# Power_PCB.net
KiCad netlist of a schematic drawn in EAGLE
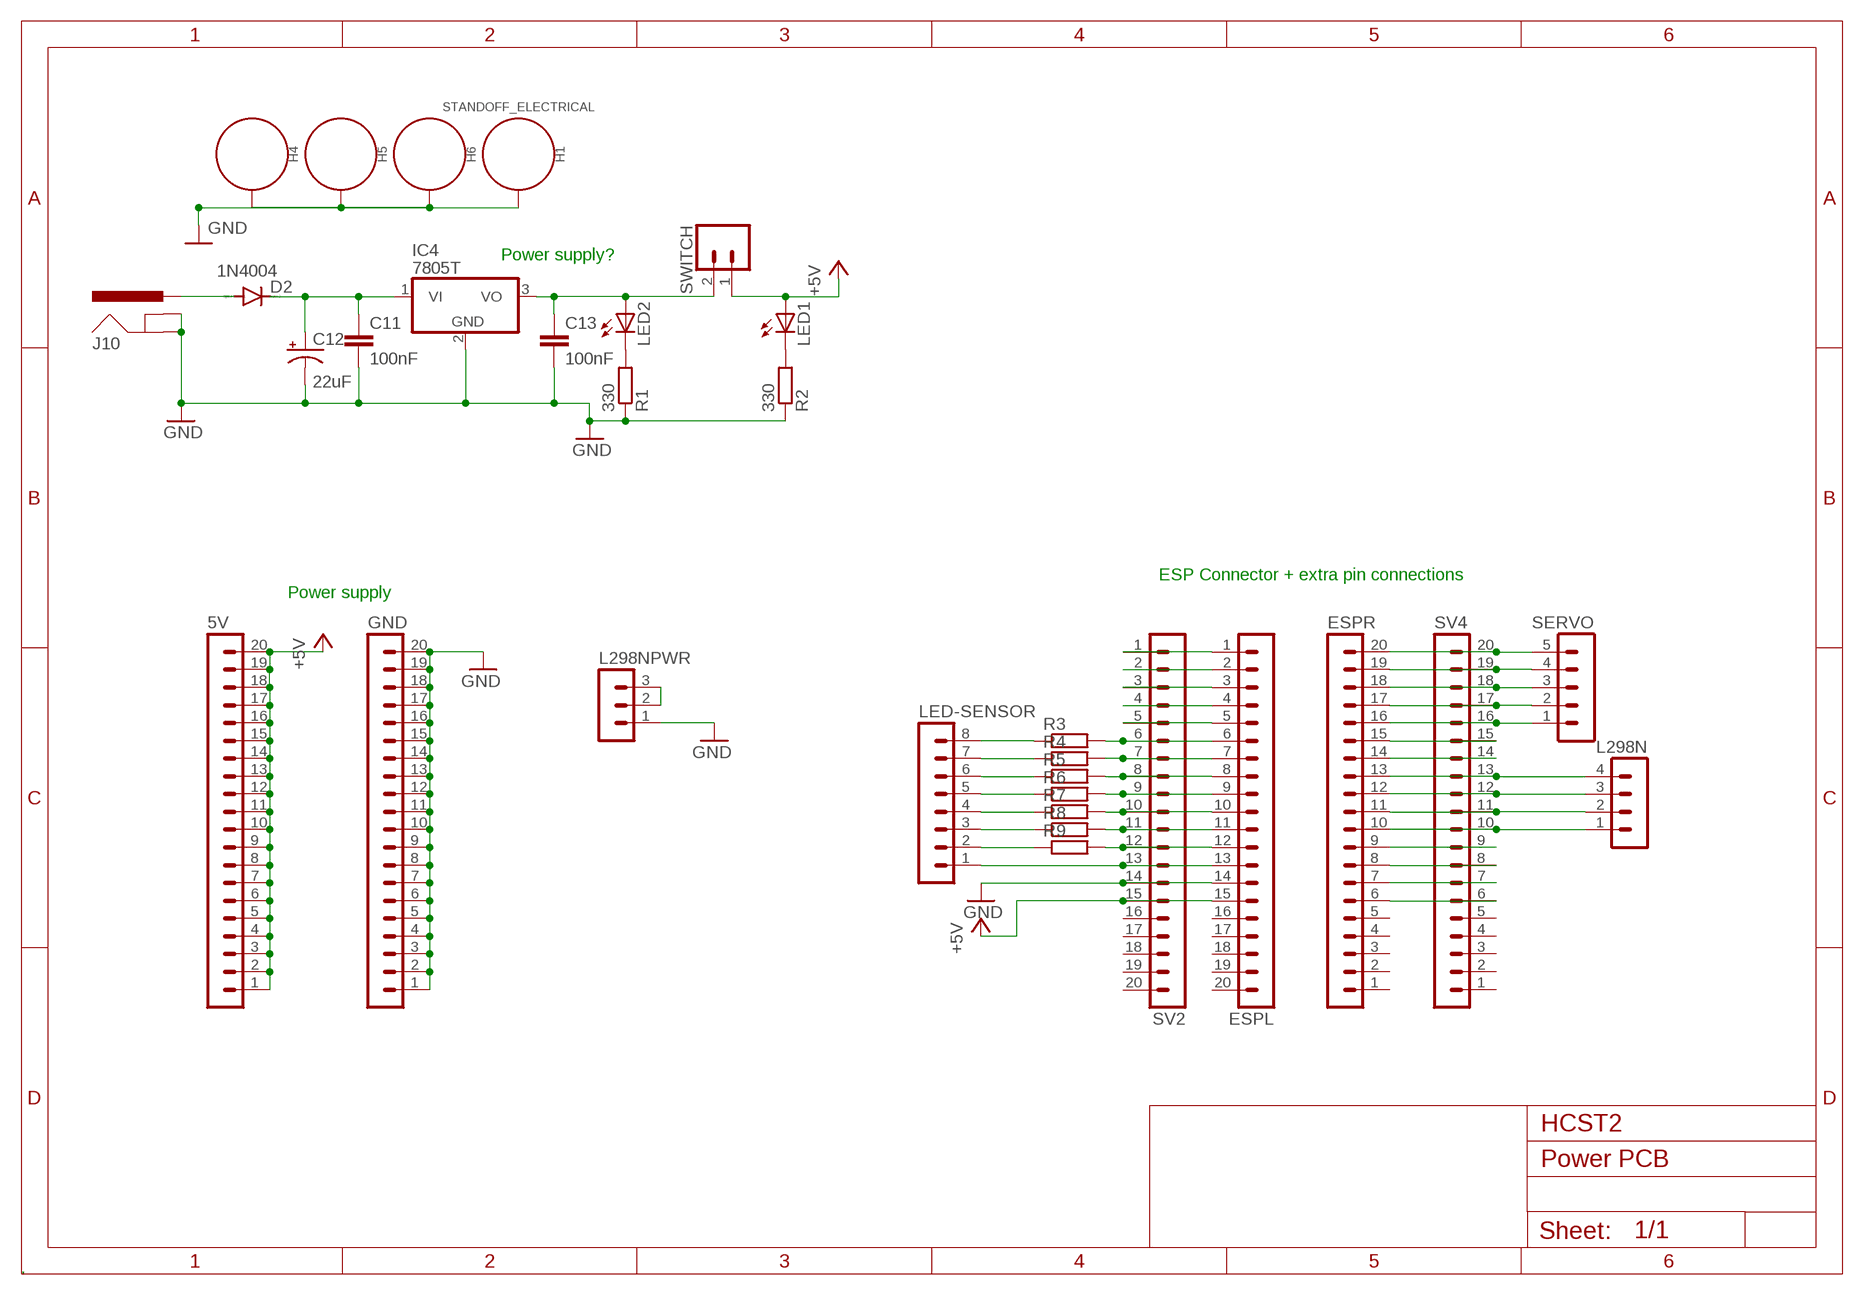
[diagram p0: schematic, sheet 1]

(export (version "E")
  (design (tool "Eeschema 10.0.6"))
  (components
    (comp (ref "5V")
      (value "MA20-1")
      (footprint "eagle-import:MA20-1")
      (libsource (lib "eagle-import") (part "MA20-1"))
    )
    (comp (ref "C11")
      (value "100nF")
      (footprint "eagle-import:C2.5-2")
      (libsource (lib "eagle-import") (part "C2.5/2"))
    )
    (comp (ref "C12")
      (value "22uF")
      (footprint "eagle-import:E2,5-7")
      (libsource (lib "eagle-import") (part "CPOL-USE2.5-7"))
    )
    (comp (ref "C13")
      (value "100nF")
      (footprint "eagle-import:C2.5-2")
      (libsource (lib "eagle-import") (part "C2.5/2"))
    )
    (comp (ref "D2")
      (value "1N4004")
      (footprint "eagle-import:DO41-10")
      (libsource (lib "eagle-import") (part "1N4004"))
    )
    (comp (ref "ESPL")
      (value "MA20-1")
      (footprint "eagle-import:MA20-1")
      (libsource (lib "eagle-import") (part "MA20-1"))
    )
    (comp (ref "ESPR")
      (value "MA20-1")
      (footprint "eagle-import:MA20-1")
      (libsource (lib "eagle-import") (part "MA20-1"))
    )
    (comp (ref "GND")
      (value "MA20-1")
      (footprint "eagle-import:MA20-1")
      (libsource (lib "eagle-import") (part "MA20-1"))
    )
    (comp (ref "H1")
      (value "STANDOFF_ELECTRICAL")
      (footprint "eagle-import:STANDOFF-ELECTRICAL")
      (libsource (lib "eagle-import") (part "STANDOFF_ELECTRICAL"))
    )
    (comp (ref "H4")
      (value "STANDOFF_ELECTRICAL")
      (footprint "eagle-import:STANDOFF-ELECTRICAL")
      (libsource (lib "eagle-import") (part "SparkFun-Hardware_519_STANDOFF_ELECTRICAL"))
    )
    (comp (ref "H5")
      (value "STANDOFF_ELECTRICAL")
      (footprint "eagle-import:STANDOFF-ELECTRICAL")
      (libsource (lib "eagle-import") (part "SparkFun-Hardware_519_STANDOFF_ELECTRICAL"))
    )
    (comp (ref "H6")
      (value "STANDOFF_ELECTRICAL")
      (footprint "eagle-import:STANDOFF-ELECTRICAL")
      (libsource (lib "eagle-import") (part "SparkFun-Hardware_519_STANDOFF_ELECTRICAL"))
    )
    (comp (ref "IC4")
      (value "7805T")
      (footprint "eagle-import:TO220H")
      (libsource (lib "eagle-import") (part "78T05"))
    )
    (comp (ref "J10")
      (value "EL311-ROBOT_SPARKFUN-CONNECTORS_POWER_JACKPTH")
      (footprint "eagle-import:EL311-ROBOT_SPARKFUN-CONNECTORS_POWER_JACK_PTH")
      (libsource (lib "eagle-import") (part "EL311-ROBOT_SPARKFUN-CONNECTORS_POWER_JACKPTH"))
    )
    (comp (ref "L298N")
      (value "MA04-1")
      (footprint "eagle-import:MA04-1")
      (libsource (lib "eagle-import") (part "MA04-1"))
    )
    (comp (ref "L298NPWR")
      (value "MA03-1")
      (footprint "eagle-import:MA03-1")
      (libsource (lib "eagle-import") (part "MA03-1"))
    )
    (comp (ref "LED-SENSOR")
      (value "MA08-1")
      (footprint "eagle-import:MA08-1")
      (libsource (lib "eagle-import") (part "MA08-1"))
    )
    (comp (ref "LED1")
      (value "LED3MM")
      (footprint "eagle-import:LED3MM")
      (libsource (lib "eagle-import") (part "LED3MM"))
    )
    (comp (ref "LED2")
      (value "LED3MM")
      (footprint "eagle-import:LED3MM")
      (libsource (lib "eagle-import") (part "LED3MM"))
    )
    (comp (ref "R1")
      (value "330")
      (footprint "eagle-import:0207_10")
      (libsource (lib "eagle-import") (part "R-EU_0207/10"))
    )
    (comp (ref "R2")
      (value "330")
      (footprint "eagle-import:0207_10")
      (libsource (lib "eagle-import") (part "R-EU_0207/10"))
    )
    (comp (ref "R3")
      (value "R-EU_0207/10")
      (footprint "eagle-import:0207_10")
      (libsource (lib "eagle-import") (part "R-EU_0207/10"))
    )
    (comp (ref "R4")
      (value "R-EU_0207/10")
      (footprint "eagle-import:0207_10")
      (libsource (lib "eagle-import") (part "R-EU_0207/10"))
    )
    (comp (ref "R5")
      (value "R-EU_0207/10")
      (footprint "eagle-import:0207_10")
      (libsource (lib "eagle-import") (part "R-EU_0207/10"))
    )
    (comp (ref "R6")
      (value "R-EU_0207/10")
      (footprint "eagle-import:0207_10")
      (libsource (lib "eagle-import") (part "R-EU_0207/10"))
    )
    (comp (ref "R7")
      (value "R-EU_0207/10")
      (footprint "eagle-import:0207_10")
      (libsource (lib "eagle-import") (part "R-EU_0207/10"))
    )
    (comp (ref "R8")
      (value "R-EU_0207/10")
      (footprint "eagle-import:0207_10")
      (libsource (lib "eagle-import") (part "R-EU_0207/10"))
    )
    (comp (ref "R9")
      (value "R-EU_0207/10")
      (footprint "eagle-import:0207_10")
      (libsource (lib "eagle-import") (part "R-EU_0207/10"))
    )
    (comp (ref "SERVO")
      (value "MA05-1")
      (footprint "eagle-import:MA05-1")
      (libsource (lib "eagle-import") (part "MA05-1"))
    )
    (comp (ref "SV2")
      (value "MA20-1")
      (footprint "eagle-import:MA20-1")
      (libsource (lib "eagle-import") (part "MA20-1"))
    )
    (comp (ref "SV4")
      (value "MA20-1")
      (footprint "eagle-import:MA20-1")
      (libsource (lib "eagle-import") (part "MA20-1"))
    )
    (comp (ref "SWITCH")
      (value "CONN_02")
      (footprint "eagle-import:1X02")
      (libsource (lib "eagle-import") (part "CONN_02"))
    )
  )
  (nets
    (net (code "1") (name "+5V") (class "Default")
      (node (ref "5V") (pin "1") (pinfunction "1_1") (pintype "passive"))
      (node (ref "5V") (pin "10") (pinfunction "10_10") (pintype "passive"))
      (node (ref "5V") (pin "11") (pinfunction "11_11") (pintype "passive"))
      (node (ref "5V") (pin "12") (pinfunction "12_12") (pintype "passive"))
      (node (ref "5V") (pin "13") (pinfunction "13_13") (pintype "passive"))
      (node (ref "5V") (pin "14") (pinfunction "14_14") (pintype "passive"))
      (node (ref "5V") (pin "15") (pinfunction "15_15") (pintype "passive"))
      (node (ref "5V") (pin "16") (pinfunction "16_16") (pintype "passive"))
      (node (ref "5V") (pin "17") (pinfunction "17_17") (pintype "passive"))
      (node (ref "5V") (pin "18") (pinfunction "18_18") (pintype "passive"))
      (node (ref "5V") (pin "19") (pinfunction "19_19") (pintype "passive"))
      (node (ref "5V") (pin "2") (pinfunction "2_2") (pintype "passive"))
      (node (ref "5V") (pin "20") (pinfunction "20_20") (pintype "passive"))
      (node (ref "5V") (pin "3") (pinfunction "3_3") (pintype "passive"))
      (node (ref "5V") (pin "4") (pinfunction "4_4") (pintype "passive"))
      (node (ref "5V") (pin "5") (pinfunction "5_5") (pintype "passive"))
      (node (ref "5V") (pin "6") (pinfunction "6_6") (pintype "passive"))
      (node (ref "5V") (pin "7") (pinfunction "7_7") (pintype "passive"))
      (node (ref "5V") (pin "8") (pinfunction "8_8") (pintype "passive"))
      (node (ref "5V") (pin "9") (pinfunction "9_9") (pintype "passive"))
      (node (ref "ESPL") (pin "15") (pinfunction "15_15") (pintype "passive"))
      (node (ref "LED1") (pin "A") (pinfunction "A_A") (pintype "passive"))
      (node (ref "SV2") (pin "15") (pinfunction "15_15") (pintype "passive"))
      (node (ref "SWITCH") (pin "1") (pinfunction "1_1") (pintype "passive"))
    )
    (net (code "2") (name "GND") (class "Default")
      (node (ref "C11") (pin "2") (pinfunction "2_2") (pintype "passive"))
      (node (ref "C12") (pin "-") (pinfunction "-_-") (pintype "passive"))
      (node (ref "C13") (pin "2") (pinfunction "2_2") (pintype "passive"))
      (node (ref "ESPL") (pin "14") (pinfunction "14_14") (pintype "passive"))
      (node (ref "GND") (pin "1") (pinfunction "1_1") (pintype "passive"))
      (node (ref "GND") (pin "10") (pinfunction "10_10") (pintype "passive"))
      (node (ref "GND") (pin "11") (pinfunction "11_11") (pintype "passive"))
      (node (ref "GND") (pin "12") (pinfunction "12_12") (pintype "passive"))
      (node (ref "GND") (pin "13") (pinfunction "13_13") (pintype "passive"))
      (node (ref "GND") (pin "14") (pinfunction "14_14") (pintype "passive"))
      (node (ref "GND") (pin "15") (pinfunction "15_15") (pintype "passive"))
      (node (ref "GND") (pin "16") (pinfunction "16_16") (pintype "passive"))
      (node (ref "GND") (pin "17") (pinfunction "17_17") (pintype "passive"))
      (node (ref "GND") (pin "18") (pinfunction "18_18") (pintype "passive"))
      (node (ref "GND") (pin "19") (pinfunction "19_19") (pintype "passive"))
      (node (ref "GND") (pin "2") (pinfunction "2_2") (pintype "passive"))
      (node (ref "GND") (pin "20") (pinfunction "20_20") (pintype "passive"))
      (node (ref "GND") (pin "3") (pinfunction "3_3") (pintype "passive"))
      (node (ref "GND") (pin "4") (pinfunction "4_4") (pintype "passive"))
      (node (ref "GND") (pin "5") (pinfunction "5_5") (pintype "passive"))
      (node (ref "GND") (pin "6") (pinfunction "6_6") (pintype "passive"))
      (node (ref "GND") (pin "7") (pinfunction "7_7") (pintype "passive"))
      (node (ref "GND") (pin "8") (pinfunction "8_8") (pintype "passive"))
      (node (ref "GND") (pin "9") (pinfunction "9_9") (pintype "passive"))
      (node (ref "H1") (pin "P1") (pinfunction "P$1_P1") (pintype "bidirectional"))
      (node (ref "H4") (pin "P1") (pinfunction "P$1_P1") (pintype "bidirectional"))
      (node (ref "H5") (pin "P1") (pinfunction "P$1_P1") (pintype "bidirectional"))
      (node (ref "H6") (pin "P1") (pinfunction "P$1_P1") (pintype "bidirectional"))
      (node (ref "IC4") (pin "2") (pinfunction "GND_2") (pintype "passive"))
      (node (ref "J10") (pin "GND") (pinfunction "GND_GND") (pintype "bidirectional"))
      (node (ref "J10") (pin "GNDBREAK") (pinfunction "GNDBREAK_GNDBREAK") (pintype "bidirectional"))
      (node (ref "L298NPWR") (pin "1") (pinfunction "1_1") (pintype "passive"))
      (node (ref "R1") (pin "1") (pinfunction "1_1") (pintype "passive"))
      (node (ref "R2") (pin "1") (pinfunction "1_1") (pintype "passive"))
      (node (ref "SV2") (pin "14") (pinfunction "14_14") (pintype "passive"))
    )
    (net (code "3") (name "Net-(D2-PadA)") (class "Default")
      (node (ref "D2") (pin "A") (pinfunction "A_A") (pintype "passive"))
      (node (ref "J10") (pin "PWR") (pinfunction "PWR_PWR") (pintype "bidirectional"))
    )
    (net (code "4") (name "Net-(ESPL-Pad1)") (class "Default")
      (node (ref "ESPL") (pin "1") (pinfunction "1_1") (pintype "passive"))
      (node (ref "SV2") (pin "1") (pinfunction "1_1") (pintype "passive"))
    )
    (net (code "5") (name "Net-(ESPL-Pad2)") (class "Default")
      (node (ref "ESPL") (pin "2") (pinfunction "2_2") (pintype "passive"))
      (node (ref "SV2") (pin "2") (pinfunction "2_2") (pintype "passive"))
    )
    (net (code "6") (name "Net-(ESPL-Pad3)") (class "Default")
      (node (ref "ESPL") (pin "3") (pinfunction "3_3") (pintype "passive"))
      (node (ref "SV2") (pin "3") (pinfunction "3_3") (pintype "passive"))
    )
    (net (code "7") (name "Net-(ESPL-Pad4)") (class "Default")
      (node (ref "ESPL") (pin "4") (pinfunction "4_4") (pintype "passive"))
      (node (ref "SV2") (pin "4") (pinfunction "4_4") (pintype "passive"))
    )
    (net (code "8") (name "Net-(ESPL-Pad5)") (class "Default")
      (node (ref "ESPL") (pin "5") (pinfunction "5_5") (pintype "passive"))
      (node (ref "SV2") (pin "5") (pinfunction "5_5") (pintype "passive"))
    )
    (net (code "9") (name "Net-(ESPL-Pad6)") (class "Default")
      (node (ref "ESPL") (pin "6") (pinfunction "6_6") (pintype "passive"))
      (node (ref "R3") (pin "2") (pinfunction "2_2") (pintype "passive"))
      (node (ref "SV2") (pin "6") (pinfunction "6_6") (pintype "passive"))
    )
    (net (code "10") (name "Net-(ESPL-Pad7)") (class "Default")
      (node (ref "ESPL") (pin "7") (pinfunction "7_7") (pintype "passive"))
      (node (ref "R4") (pin "2") (pinfunction "2_2") (pintype "passive"))
      (node (ref "SV2") (pin "7") (pinfunction "7_7") (pintype "passive"))
    )
    (net (code "11") (name "Net-(ESPL-Pad8)") (class "Default")
      (node (ref "ESPL") (pin "8") (pinfunction "8_8") (pintype "passive"))
      (node (ref "R5") (pin "2") (pinfunction "2_2") (pintype "passive"))
      (node (ref "SV2") (pin "8") (pinfunction "8_8") (pintype "passive"))
    )
    (net (code "12") (name "Net-(ESPL-Pad9)") (class "Default")
      (node (ref "ESPL") (pin "9") (pinfunction "9_9") (pintype "passive"))
      (node (ref "R6") (pin "2") (pinfunction "2_2") (pintype "passive"))
      (node (ref "SV2") (pin "9") (pinfunction "9_9") (pintype "passive"))
    )
    (net (code "13") (name "Net-(ESPL-Pad10)") (class "Default")
      (node (ref "ESPL") (pin "10") (pinfunction "10_10") (pintype "passive"))
      (node (ref "R7") (pin "2") (pinfunction "2_2") (pintype "passive"))
      (node (ref "SV2") (pin "10") (pinfunction "10_10") (pintype "passive"))
    )
    (net (code "14") (name "Net-(ESPL-Pad11)") (class "Default")
      (node (ref "ESPL") (pin "11") (pinfunction "11_11") (pintype "passive"))
      (node (ref "R8") (pin "2") (pinfunction "2_2") (pintype "passive"))
      (node (ref "SV2") (pin "11") (pinfunction "11_11") (pintype "passive"))
    )
    (net (code "15") (name "Net-(ESPL-Pad12)") (class "Default")
      (node (ref "ESPL") (pin "12") (pinfunction "12_12") (pintype "passive"))
      (node (ref "R9") (pin "2") (pinfunction "2_2") (pintype "passive"))
      (node (ref "SV2") (pin "12") (pinfunction "12_12") (pintype "passive"))
    )
    (net (code "16") (name "Net-(ESPL-Pad13)") (class "Default")
      (node (ref "ESPL") (pin "13") (pinfunction "13_13") (pintype "passive"))
      (node (ref "LED-SENSOR") (pin "1") (pinfunction "1_1") (pintype "passive"))
      (node (ref "SV2") (pin "13") (pinfunction "13_13") (pintype "passive"))
    )
    (net (code "17") (name "Net-(ESPR-Pad6)") (class "Default")
      (node (ref "ESPR") (pin "6") (pinfunction "6_6") (pintype "passive"))
      (node (ref "SV4") (pin "6") (pinfunction "6_6") (pintype "passive"))
    )
    (net (code "18") (name "Net-(ESPR-Pad7)") (class "Default")
      (node (ref "ESPR") (pin "7") (pinfunction "7_7") (pintype "passive"))
      (node (ref "SV4") (pin "7") (pinfunction "7_7") (pintype "passive"))
    )
    (net (code "19") (name "Net-(ESPR-Pad8)") (class "Default")
      (node (ref "ESPR") (pin "8") (pinfunction "8_8") (pintype "passive"))
      (node (ref "SV4") (pin "8") (pinfunction "8_8") (pintype "passive"))
    )
    (net (code "20") (name "Net-(ESPR-Pad9)") (class "Default")
      (node (ref "ESPR") (pin "9") (pinfunction "9_9") (pintype "passive"))
      (node (ref "SV4") (pin "9") (pinfunction "9_9") (pintype "passive"))
    )
    (net (code "21") (name "Net-(ESPR-Pad10)") (class "Default")
      (node (ref "ESPR") (pin "10") (pinfunction "10_10") (pintype "passive"))
      (node (ref "L298N") (pin "1") (pinfunction "1_1") (pintype "passive"))
      (node (ref "SV4") (pin "10") (pinfunction "10_10") (pintype "passive"))
    )
    (net (code "22") (name "Net-(ESPR-Pad11)") (class "Default")
      (node (ref "ESPR") (pin "11") (pinfunction "11_11") (pintype "passive"))
      (node (ref "L298N") (pin "2") (pinfunction "2_2") (pintype "passive"))
      (node (ref "SV4") (pin "11") (pinfunction "11_11") (pintype "passive"))
    )
    (net (code "23") (name "Net-(ESPR-Pad12)") (class "Default")
      (node (ref "ESPR") (pin "12") (pinfunction "12_12") (pintype "passive"))
      (node (ref "L298N") (pin "3") (pinfunction "3_3") (pintype "passive"))
      (node (ref "SV4") (pin "12") (pinfunction "12_12") (pintype "passive"))
    )
    (net (code "24") (name "Net-(ESPR-Pad13)") (class "Default")
      (node (ref "ESPR") (pin "13") (pinfunction "13_13") (pintype "passive"))
      (node (ref "L298N") (pin "4") (pinfunction "4_4") (pintype "passive"))
      (node (ref "SV4") (pin "13") (pinfunction "13_13") (pintype "passive"))
    )
    (net (code "25") (name "Net-(ESPR-Pad14)") (class "Default")
      (node (ref "ESPR") (pin "14") (pinfunction "14_14") (pintype "passive"))
      (node (ref "SV4") (pin "14") (pinfunction "14_14") (pintype "passive"))
    )
    (net (code "26") (name "Net-(ESPR-Pad15)") (class "Default")
      (node (ref "ESPR") (pin "15") (pinfunction "15_15") (pintype "passive"))
      (node (ref "SV4") (pin "15") (pinfunction "15_15") (pintype "passive"))
    )
    (net (code "27") (name "Net-(ESPR-Pad16)") (class "Default")
      (node (ref "ESPR") (pin "16") (pinfunction "16_16") (pintype "passive"))
      (node (ref "SERVO") (pin "1") (pinfunction "1_1") (pintype "passive"))
      (node (ref "SV4") (pin "16") (pinfunction "16_16") (pintype "passive"))
    )
    (net (code "28") (name "Net-(ESPR-Pad17)") (class "Default")
      (node (ref "ESPR") (pin "17") (pinfunction "17_17") (pintype "passive"))
      (node (ref "SERVO") (pin "2") (pinfunction "2_2") (pintype "passive"))
      (node (ref "SV4") (pin "17") (pinfunction "17_17") (pintype "passive"))
    )
    (net (code "29") (name "Net-(ESPR-Pad18)") (class "Default")
      (node (ref "ESPR") (pin "18") (pinfunction "18_18") (pintype "passive"))
      (node (ref "SERVO") (pin "3") (pinfunction "3_3") (pintype "passive"))
      (node (ref "SV4") (pin "18") (pinfunction "18_18") (pintype "passive"))
    )
    (net (code "30") (name "Net-(ESPR-Pad19)") (class "Default")
      (node (ref "ESPR") (pin "19") (pinfunction "19_19") (pintype "passive"))
      (node (ref "SERVO") (pin "4") (pinfunction "4_4") (pintype "passive"))
      (node (ref "SV4") (pin "19") (pinfunction "19_19") (pintype "passive"))
    )
    (net (code "31") (name "Net-(ESPR-Pad20)") (class "Default")
      (node (ref "ESPR") (pin "20") (pinfunction "20_20") (pintype "passive"))
      (node (ref "SERVO") (pin "5") (pinfunction "5_5") (pintype "passive"))
      (node (ref "SV4") (pin "20") (pinfunction "20_20") (pintype "passive"))
    )
    (net (code "32") (name "Net-(IC4-VI)") (class "Default")
      (node (ref "C11") (pin "1") (pinfunction "1_1") (pintype "passive"))
      (node (ref "C12") (pin "+") (pinfunction "+_+") (pintype "passive"))
      (node (ref "D2") (pin "C") (pinfunction "C_C") (pintype "passive"))
      (node (ref "IC4") (pin "1") (pinfunction "VI_1") (pintype "input"))
    )
    (net (code "33") (name "Net-(IC4-VO)") (class "Default")
      (node (ref "C13") (pin "1") (pinfunction "1_1") (pintype "passive"))
      (node (ref "IC4") (pin "3") (pinfunction "VO_3") (pintype "passive"))
      (node (ref "LED2") (pin "A") (pinfunction "A_A") (pintype "passive"))
      (node (ref "SWITCH") (pin "2") (pinfunction "2_2") (pintype "passive"))
    )
    (net (code "34") (name "Net-(L298NPWR-Pad2)") (class "Default")
      (node (ref "L298NPWR") (pin "2") (pinfunction "2_2") (pintype "passive"))
      (node (ref "L298NPWR") (pin "3") (pinfunction "3_3") (pintype "passive"))
    )
    (net (code "35") (name "Net-(LED-SENSOR-Pad2)") (class "Default")
      (node (ref "LED-SENSOR") (pin "2") (pinfunction "2_2") (pintype "passive"))
      (node (ref "R9") (pin "1") (pinfunction "1_1") (pintype "passive"))
    )
    (net (code "36") (name "Net-(LED-SENSOR-Pad3)") (class "Default")
      (node (ref "LED-SENSOR") (pin "3") (pinfunction "3_3") (pintype "passive"))
      (node (ref "R8") (pin "1") (pinfunction "1_1") (pintype "passive"))
    )
    (net (code "37") (name "Net-(LED-SENSOR-Pad4)") (class "Default")
      (node (ref "LED-SENSOR") (pin "4") (pinfunction "4_4") (pintype "passive"))
      (node (ref "R7") (pin "1") (pinfunction "1_1") (pintype "passive"))
    )
    (net (code "38") (name "Net-(LED-SENSOR-Pad5)") (class "Default")
      (node (ref "LED-SENSOR") (pin "5") (pinfunction "5_5") (pintype "passive"))
      (node (ref "R6") (pin "1") (pinfunction "1_1") (pintype "passive"))
    )
    (net (code "39") (name "Net-(LED-SENSOR-Pad6)") (class "Default")
      (node (ref "LED-SENSOR") (pin "6") (pinfunction "6_6") (pintype "passive"))
      (node (ref "R5") (pin "1") (pinfunction "1_1") (pintype "passive"))
    )
    (net (code "40") (name "Net-(LED-SENSOR-Pad7)") (class "Default")
      (node (ref "LED-SENSOR") (pin "7") (pinfunction "7_7") (pintype "passive"))
      (node (ref "R4") (pin "1") (pinfunction "1_1") (pintype "passive"))
    )
    (net (code "41") (name "Net-(LED-SENSOR-Pad8)") (class "Default")
      (node (ref "LED-SENSOR") (pin "8") (pinfunction "8_8") (pintype "passive"))
      (node (ref "R3") (pin "1") (pinfunction "1_1") (pintype "passive"))
    )
    (net (code "42") (name "Net-(LED1-C)") (class "Default")
      (node (ref "LED1") (pin "K") (pinfunction "C_K") (pintype "passive"))
      (node (ref "R2") (pin "2") (pinfunction "2_2") (pintype "passive"))
    )
    (net (code "43") (name "Net-(LED2-C)") (class "Default")
      (node (ref "LED2") (pin "K") (pinfunction "C_K") (pintype "passive"))
      (node (ref "R1") (pin "2") (pinfunction "2_2") (pintype "passive"))
    )
    (net (code "44") (name "unconnected-(ESPL-Pad16)") (class "Default")
      (node (ref "ESPL") (pin "16") (pinfunction "16_16") (pintype "passive"))
    )
    (net (code "45") (name "unconnected-(ESPL-Pad17)") (class "Default")
      (node (ref "ESPL") (pin "17") (pinfunction "17_17") (pintype "passive"))
    )
    (net (code "46") (name "unconnected-(ESPL-Pad18)") (class "Default")
      (node (ref "ESPL") (pin "18") (pinfunction "18_18") (pintype "passive"))
    )
    (net (code "47") (name "unconnected-(ESPL-Pad19)") (class "Default")
      (node (ref "ESPL") (pin "19") (pinfunction "19_19") (pintype "passive"))
    )
    (net (code "48") (name "unconnected-(ESPL-Pad20)") (class "Default")
      (node (ref "ESPL") (pin "20") (pinfunction "20_20") (pintype "passive"))
    )
    (net (code "49") (name "unconnected-(ESPR-Pad1)") (class "Default")
      (node (ref "ESPR") (pin "1") (pinfunction "1_1") (pintype "passive"))
    )
    (net (code "50") (name "unconnected-(ESPR-Pad2)") (class "Default")
      (node (ref "ESPR") (pin "2") (pinfunction "2_2") (pintype "passive"))
    )
    (net (code "51") (name "unconnected-(ESPR-Pad3)") (class "Default")
      (node (ref "ESPR") (pin "3") (pinfunction "3_3") (pintype "passive"))
    )
    (net (code "52") (name "unconnected-(ESPR-Pad4)") (class "Default")
      (node (ref "ESPR") (pin "4") (pinfunction "4_4") (pintype "passive"))
    )
    (net (code "53") (name "unconnected-(ESPR-Pad5)") (class "Default")
      (node (ref "ESPR") (pin "5") (pinfunction "5_5") (pintype "passive"))
    )
    (net (code "54") (name "unconnected-(SV2-Pad16)") (class "Default")
      (node (ref "SV2") (pin "16") (pinfunction "16_16") (pintype "passive"))
    )
    (net (code "55") (name "unconnected-(SV2-Pad17)") (class "Default")
      (node (ref "SV2") (pin "17") (pinfunction "17_17") (pintype "passive"))
    )
    (net (code "56") (name "unconnected-(SV2-Pad18)") (class "Default")
      (node (ref "SV2") (pin "18") (pinfunction "18_18") (pintype "passive"))
    )
    (net (code "57") (name "unconnected-(SV2-Pad19)") (class "Default")
      (node (ref "SV2") (pin "19") (pinfunction "19_19") (pintype "passive"))
    )
    (net (code "58") (name "unconnected-(SV2-Pad20)") (class "Default")
      (node (ref "SV2") (pin "20") (pinfunction "20_20") (pintype "passive"))
    )
    (net (code "59") (name "unconnected-(SV4-Pad1)") (class "Default")
      (node (ref "SV4") (pin "1") (pinfunction "1_1") (pintype "passive"))
    )
    (net (code "60") (name "unconnected-(SV4-Pad2)") (class "Default")
      (node (ref "SV4") (pin "2") (pinfunction "2_2") (pintype "passive"))
    )
    (net (code "61") (name "unconnected-(SV4-Pad3)") (class "Default")
      (node (ref "SV4") (pin "3") (pinfunction "3_3") (pintype "passive"))
    )
    (net (code "62") (name "unconnected-(SV4-Pad4)") (class "Default")
      (node (ref "SV4") (pin "4") (pinfunction "4_4") (pintype "passive"))
    )
    (net (code "63") (name "unconnected-(SV4-Pad5)") (class "Default")
      (node (ref "SV4") (pin "5") (pinfunction "5_5") (pintype "passive"))
    )
  )
)
